# schemat.net
KiCad netlist of a schematic drawn in EAGLE
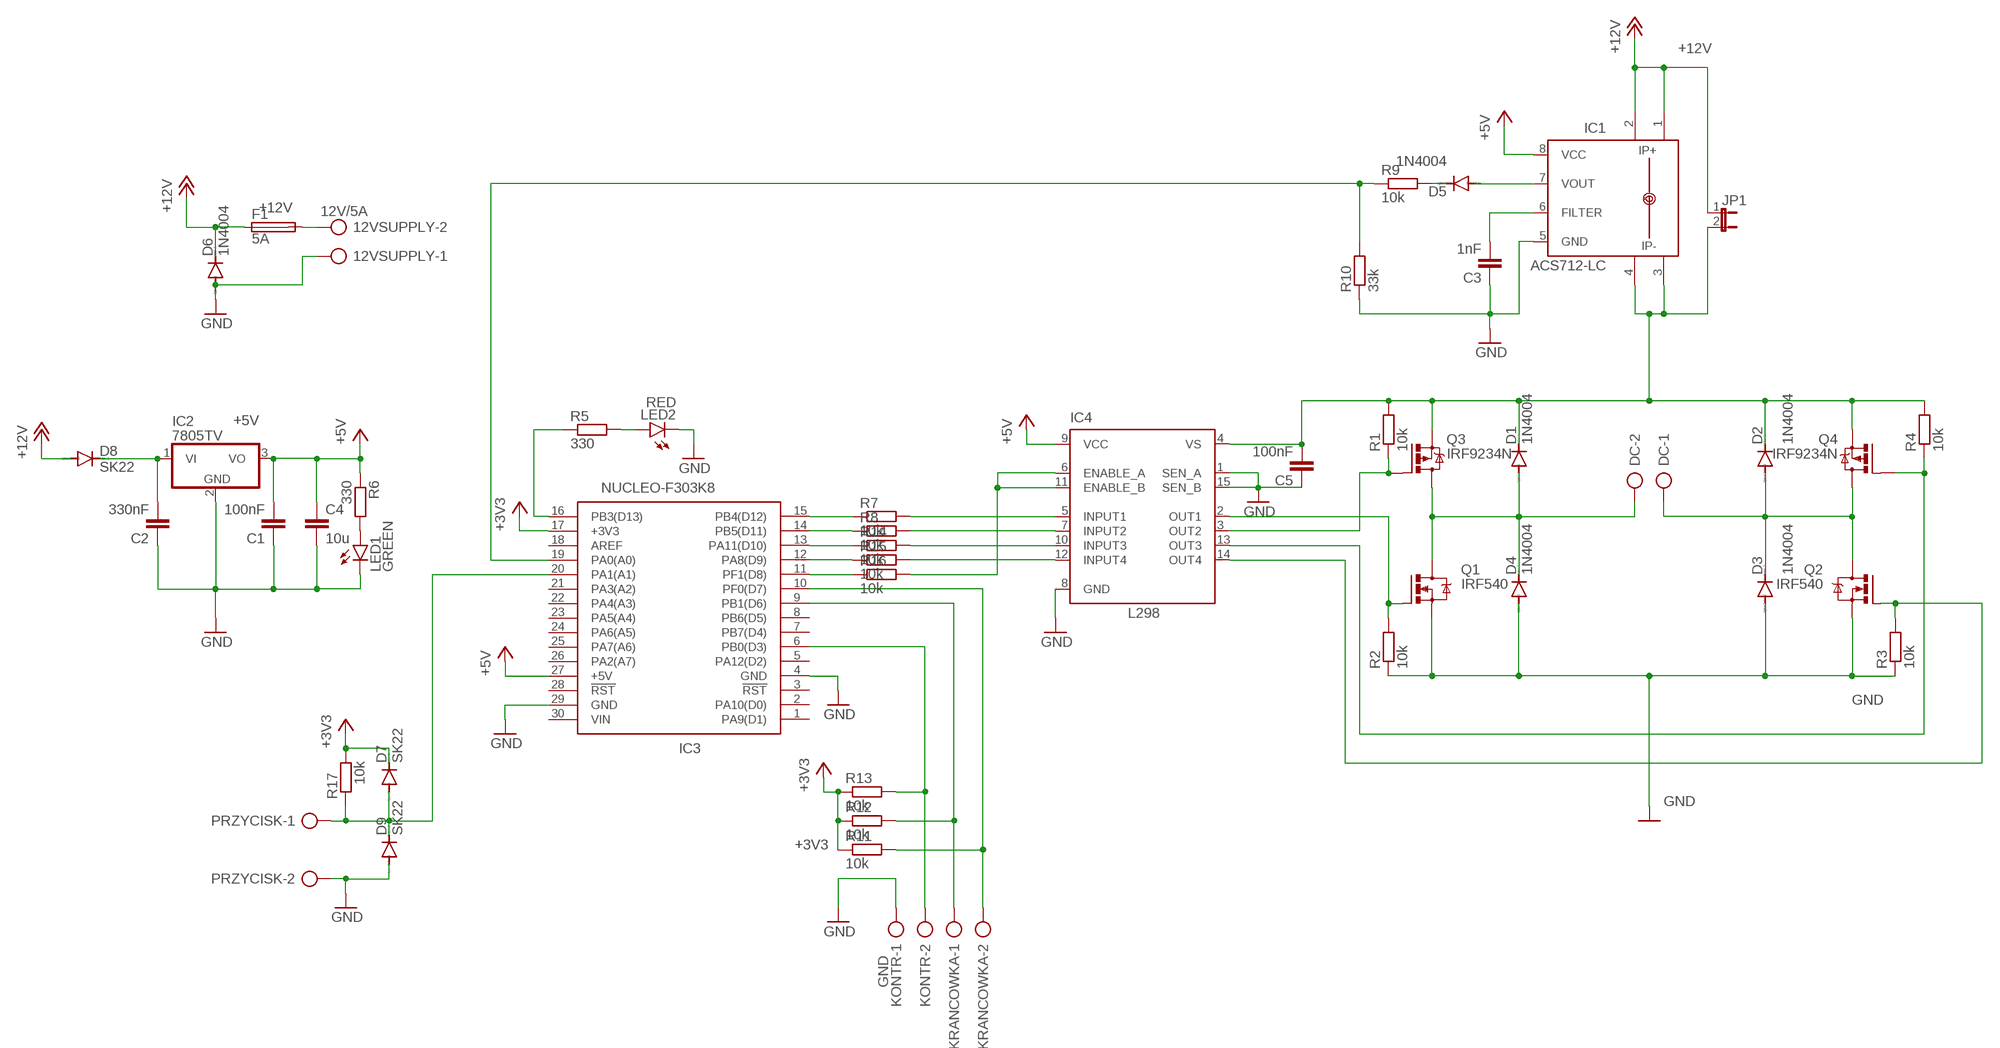
[diagram p0: schematic, sheet 1]

(export (version "E")
  (design (tool "Eeschema 10.0.6"))
  (components
    (comp (ref "12VSUPPLY")
      (value "12V/5A")
      (footprint "eagle-import:AK500_2-H")
      (libsource (lib "eagle-import") (part "AK500/2-H"))
    )
    (comp (ref "C1")
      (value "100nF")
      (footprint "eagle-import:C2.5-2")
      (libsource (lib "eagle-import") (part "C2.5/2"))
    )
    (comp (ref "C2")
      (value "330nF")
      (footprint "eagle-import:C2.5-2")
      (libsource (lib "eagle-import") (part "C2.5/2"))
    )
    (comp (ref "C3")
      (value "1nF")
      (footprint "eagle-import:C025-024X044")
      (libsource (lib "eagle-import") (part "C-EU025-024X044"))
    )
    (comp (ref "C4")
      (value "10u")
      (footprint "eagle-import:C025-024X044")
      (libsource (lib "eagle-import") (part "C-EU025-024X044"))
    )
    (comp (ref "C5")
      (value "100nF")
      (footprint "eagle-import:C2.5-2")
      (libsource (lib "eagle-import") (part "C2.5/2"))
    )
    (comp (ref "D1")
      (value "1N4004")
      (footprint "eagle-import:DO41-10")
      (libsource (lib "eagle-import") (part "1N4004"))
    )
    (comp (ref "D2")
      (value "1N4004")
      (footprint "eagle-import:DO41-10")
      (libsource (lib "eagle-import") (part "1N4004"))
    )
    (comp (ref "D3")
      (value "1N4004")
      (footprint "eagle-import:DO41-10")
      (libsource (lib "eagle-import") (part "1N4004"))
    )
    (comp (ref "D4")
      (value "1N4004")
      (footprint "eagle-import:DO41-10")
      (libsource (lib "eagle-import") (part "1N4004"))
    )
    (comp (ref "D5")
      (value "1N4004")
      (footprint "eagle-import:DO41-10")
      (libsource (lib "eagle-import") (part "1N4004"))
    )
    (comp (ref "D6")
      (value "1N4004")
      (footprint "eagle-import:DO41-10")
      (libsource (lib "eagle-import") (part "1N4004"))
    )
    (comp (ref "D7")
      (value "SK22")
      (footprint "eagle-import:SMB")
      (libsource (lib "eagle-import") (part "ES2D"))
    )
    (comp (ref "D8")
      (value "SK22")
      (footprint "eagle-import:SMB")
      (libsource (lib "eagle-import") (part "ES2D"))
    )
    (comp (ref "D9")
      (value "SK22")
      (footprint "eagle-import:SMB")
      (libsource (lib "eagle-import") (part "ES2D"))
    )
    (comp (ref "DC")
      (value "AK500/2-H")
      (footprint "eagle-import:AK500_2-H")
      (libsource (lib "eagle-import") (part "AK500/2-H"))
    )
    (comp (ref "F1")
      (value "5A")
      (footprint "eagle-import:TR5")
      (libsource (lib "eagle-import") (part "TR5"))
    )
    (comp (ref "IC1")
      (value "ACS712-LC")
      (footprint "eagle-import:SOIC8")
      (libsource (lib "eagle-import") (part "ACS712-LC"))
    )
    (comp (ref "IC2")
      (value "7805TV")
      (footprint "eagle-import:TO220V")
      (libsource (lib "eagle-import") (part "78TV05"))
    )
    (comp (ref "IC3")
      (value "NUCLEO-F303K8")
      (footprint "eagle-import:DIPS1524W66P254L5029H1500Q30N")
      (fields (field (name "RS_PART_NUMBER") "9092862"))
      (libsource (lib "eagle-import") (part "NUCLEO-F303K8"))
    )
    (comp (ref "IC4")
      (value "L298")
      (footprint "eagle-import:MULTIWATT-15")
      (fields (field (name "MPN") "L298N"))
      (libsource (lib "eagle-import") (part "L298"))
    )
    (comp (ref "JP1")
      (value "JP1E")
      (footprint "eagle-import:JP1")
      (libsource (lib "eagle-import") (part "JP1E"))
    )
    (comp (ref "KONTR")
      (value "GND")
      (footprint "eagle-import:AK500_2-H")
      (libsource (lib "eagle-import") (part "AK500/2-H"))
    )
    (comp (ref "KRANCOWKA")
      (value "AK500/2-H")
      (footprint "eagle-import:AK500_2-H")
      (libsource (lib "eagle-import") (part "AK500/2-H"))
    )
    (comp (ref "LED1")
      (value "GREEN")
      (footprint "eagle-import:LED3MM")
      (libsource (lib "eagle-import") (part "LED3MM"))
    )
    (comp (ref "LED2")
      (value "RED")
      (footprint "eagle-import:LED3MM")
      (libsource (lib "eagle-import") (part "LED3MM"))
    )
    (comp (ref "PRZYCISK")
      (value "AK500/2-H")
      (footprint "eagle-import:AK500_2-H")
      (libsource (lib "eagle-import") (part "AK500/2-H"))
    )
    (comp (ref "Q1")
      (value "IRF540")
      (footprint "eagle-import:TO220BV")
      (libsource (lib "eagle-import") (part "IRF540"))
    )
    (comp (ref "Q2")
      (value "IRF540")
      (footprint "eagle-import:TO220BV")
      (libsource (lib "eagle-import") (part "IRF540"))
    )
    (comp (ref "Q3")
      (value "IRF9234N")
      (footprint "eagle-import:TO220BV")
      (libsource (lib "eagle-import") (part "IRF9530"))
    )
    (comp (ref "Q4")
      (value "IRF9234N")
      (footprint "eagle-import:TO220BV")
      (libsource (lib "eagle-import") (part "IRF9530"))
    )
    (comp (ref "R1")
      (value "10k")
      (footprint "eagle-import:R1206")
      (libsource (lib "eagle-import") (part "R-EU_R1206"))
    )
    (comp (ref "R2")
      (value "10k")
      (footprint "eagle-import:R1206")
      (libsource (lib "eagle-import") (part "R-EU_R1206"))
    )
    (comp (ref "R3")
      (value "10k")
      (footprint "eagle-import:R1206")
      (libsource (lib "eagle-import") (part "R-EU_R1206"))
    )
    (comp (ref "R4")
      (value "10k")
      (footprint "eagle-import:R1206")
      (libsource (lib "eagle-import") (part "R-EU_R1206"))
    )
    (comp (ref "R5")
      (value "330")
      (footprint "eagle-import:R1206")
      (libsource (lib "eagle-import") (part "R-EU_R1206"))
    )
    (comp (ref "R6")
      (value "330")
      (footprint "eagle-import:R1206")
      (libsource (lib "eagle-import") (part "R-EU_R1206"))
    )
    (comp (ref "R7")
      (value "10k")
      (footprint "eagle-import:R1206")
      (libsource (lib "eagle-import") (part "R-EU_R1206"))
    )
    (comp (ref "R8")
      (value "10k")
      (footprint "eagle-import:R1206")
      (libsource (lib "eagle-import") (part "R-EU_R1206"))
    )
    (comp (ref "R9")
      (value "10k")
      (footprint "eagle-import:R1206")
      (libsource (lib "eagle-import") (part "R-EU_R1206"))
    )
    (comp (ref "R10")
      (value "33k")
      (footprint "eagle-import:R1206")
      (libsource (lib "eagle-import") (part "R-EU_R1206"))
    )
    (comp (ref "R11")
      (value "10k")
      (footprint "eagle-import:R1206")
      (libsource (lib "eagle-import") (part "R-EU_R1206"))
    )
    (comp (ref "R12")
      (value "10k")
      (footprint "eagle-import:R1206")
      (libsource (lib "eagle-import") (part "R-EU_R1206"))
    )
    (comp (ref "R13")
      (value "10k")
      (footprint "eagle-import:R1206")
      (libsource (lib "eagle-import") (part "R-EU_R1206"))
    )
    (comp (ref "R14")
      (value "10k")
      (footprint "eagle-import:R1206")
      (libsource (lib "eagle-import") (part "R-EU_R1206"))
    )
    (comp (ref "R15")
      (value "10k")
      (footprint "eagle-import:R1206")
      (libsource (lib "eagle-import") (part "R-EU_R1206"))
    )
    (comp (ref "R16")
      (value "10k")
      (footprint "eagle-import:R1206")
      (libsource (lib "eagle-import") (part "R-EU_R1206"))
    )
    (comp (ref "R17")
      (value "10k")
      (footprint "eagle-import:R1206")
      (libsource (lib "eagle-import") (part "R-EU_R1206"))
    )
  )
  (nets
    (net (code "1") (name "+3V3") (class "Default")
      (node (ref "D7") (pin "C") (pinfunction "C_C") (pintype "passive"))
      (node (ref "IC3") (pin "17") (pinfunction "+3V3_17") (pintype "passive"))
      (node (ref "R11") (pin "1") (pinfunction "1_1") (pintype "passive"))
      (node (ref "R12") (pin "1") (pinfunction "1_1") (pintype "passive"))
      (node (ref "R13") (pin "1") (pinfunction "1_1") (pintype "passive"))
      (node (ref "R17") (pin "2") (pinfunction "2_2") (pintype "passive"))
    )
    (net (code "2") (name "+5V") (class "Default")
      (node (ref "C1") (pin "2") (pinfunction "2_2") (pintype "passive"))
      (node (ref "C4") (pin "1") (pinfunction "1_1") (pintype "passive"))
      (node (ref "IC1") (pin "8") (pinfunction "VCC_8") (pintype "power_in"))
      (node (ref "IC2") (pin "3") (pinfunction "VO_3") (pintype "passive"))
      (node (ref "IC3") (pin "27") (pinfunction "+5V_27") (pintype "passive"))
      (node (ref "IC4") (pin "9") (pinfunction "VCC_9") (pintype "power_in"))
      (node (ref "R6") (pin "1") (pinfunction "1_1") (pintype "passive"))
    )
    (net (code "3") (name "+12V") (class "Default")
      (node (ref "D6") (pin "C") (pinfunction "C_C") (pintype "passive"))
      (node (ref "D8") (pin "A") (pinfunction "A_A") (pintype "passive"))
      (node (ref "F1") (pin "1") (pinfunction "1_1") (pintype "passive"))
      (node (ref "IC1") (pin "1") (pinfunction "IP+_1") (pintype "passive"))
      (node (ref "IC1") (pin "2") (pinfunction "IP+1_2") (pintype "passive"))
      (node (ref "JP1") (pin "1") (pinfunction "1_1") (pintype "passive"))
    )
    (net (code "4") (name "GND") (class "Default")
      (node (ref "12VSUPPLY") (pin "1") (pinfunction "KL_1") (pintype "passive"))
      (node (ref "C1") (pin "1") (pinfunction "1_1") (pintype "passive"))
      (node (ref "C2") (pin "1") (pinfunction "1_1") (pintype "passive"))
      (node (ref "C3") (pin "1") (pinfunction "1_1") (pintype "passive"))
      (node (ref "C4") (pin "2") (pinfunction "2_2") (pintype "passive"))
      (node (ref "C5") (pin "1") (pinfunction "1_1") (pintype "passive"))
      (node (ref "D3") (pin "A") (pinfunction "A_A") (pintype "passive"))
      (node (ref "D4") (pin "A") (pinfunction "A_A") (pintype "passive"))
      (node (ref "D6") (pin "A") (pinfunction "A_A") (pintype "passive"))
      (node (ref "D9") (pin "A") (pinfunction "A_A") (pintype "passive"))
      (node (ref "IC1") (pin "5") (pinfunction "GND_5") (pintype "power_in"))
      (node (ref "IC2") (pin "2") (pinfunction "GND_2") (pintype "passive"))
      (node (ref "IC3") (pin "29") (pinfunction "GND_29") (pintype "passive"))
      (node (ref "IC3") (pin "4") (pinfunction "GND_4") (pintype "passive"))
      (node (ref "IC4") (pin "1") (pinfunction "SEN_A_1") (pintype "input"))
      (node (ref "IC4") (pin "15") (pinfunction "SEN_B_15") (pintype "input"))
      (node (ref "IC4") (pin "8") (pinfunction "GND_8") (pintype "power_in"))
      (node (ref "KONTR") (pin "1") (pinfunction "KL_1") (pintype "passive"))
      (node (ref "LED1") (pin "K") (pinfunction "C_K") (pintype "passive"))
      (node (ref "LED2") (pin "K") (pinfunction "C_K") (pintype "passive"))
      (node (ref "PRZYCISK") (pin "2") (pinfunction "KL_2") (pintype "passive"))
      (node (ref "Q1") (pin "S") (pinfunction "S_S") (pintype "passive"))
      (node (ref "Q2") (pin "S") (pinfunction "S_S") (pintype "passive"))
      (node (ref "R10") (pin "1") (pinfunction "1_1") (pintype "passive"))
      (node (ref "R2") (pin "1") (pinfunction "1_1") (pintype "passive"))
      (node (ref "R3") (pin "1") (pinfunction "1_1") (pintype "passive"))
    )
    (net (code "5") (name "Net-(12VSUPPLYB-KL)") (class "Default")
      (node (ref "12VSUPPLY") (pin "2") (pinfunction "KL_2") (pintype "passive"))
      (node (ref "F1") (pin "2") (pinfunction "2_2") (pintype "passive"))
    )
    (net (code "6") (name "Net-(D5-PadC)") (class "Default")
      (node (ref "D5") (pin "C") (pinfunction "C_C") (pintype "passive"))
      (node (ref "R9") (pin "2") (pinfunction "2_2") (pintype "passive"))
    )
    (net (code "7") (name "Net-(DCA-KL)") (class "Default")
      (node (ref "D2") (pin "A") (pinfunction "A_A") (pintype "passive"))
      (node (ref "D3") (pin "C") (pinfunction "C_C") (pintype "passive"))
      (node (ref "DC") (pin "1") (pinfunction "KL_1") (pintype "passive"))
      (node (ref "Q2") (pin "D") (pinfunction "D_D") (pintype "passive"))
      (node (ref "Q4") (pin "D") (pinfunction "D_D") (pintype "passive"))
    )
    (net (code "8") (name "Net-(DCB-KL)") (class "Default")
      (node (ref "D1") (pin "A") (pinfunction "A_A") (pintype "passive"))
      (node (ref "D4") (pin "C") (pinfunction "C_C") (pintype "passive"))
      (node (ref "DC") (pin "2") (pinfunction "KL_2") (pintype "passive"))
      (node (ref "Q1") (pin "D") (pinfunction "D_D") (pintype "passive"))
      (node (ref "Q3") (pin "D") (pinfunction "D_D") (pintype "passive"))
    )
    (net (code "9") (name "Net-(IC1-FILTER)") (class "Default")
      (node (ref "C3") (pin "2") (pinfunction "2_2") (pintype "passive"))
      (node (ref "IC1") (pin "6") (pinfunction "FILTER_6") (pintype "bidirectional"))
    )
    (net (code "10") (name "Net-(IC1-IP-)") (class "Default")
      (node (ref "C5") (pin "2") (pinfunction "2_2") (pintype "passive"))
      (node (ref "D1") (pin "C") (pinfunction "C_C") (pintype "passive"))
      (node (ref "D2") (pin "C") (pinfunction "C_C") (pintype "passive"))
      (node (ref "IC1") (pin "3") (pinfunction "IP-_3") (pintype "passive"))
      (node (ref "IC1") (pin "4") (pinfunction "IP-1_4") (pintype "passive"))
      (node (ref "IC4") (pin "4") (pinfunction "VS_4") (pintype "power_in"))
      (node (ref "JP1") (pin "2") (pinfunction "2_2") (pintype "passive"))
      (node (ref "Q3") (pin "S") (pinfunction "S_S") (pintype "passive"))
      (node (ref "Q4") (pin "S") (pinfunction "S_S") (pintype "passive"))
      (node (ref "R1") (pin "2") (pinfunction "2_2") (pintype "passive"))
      (node (ref "R4") (pin "2") (pinfunction "2_2") (pintype "passive"))
    )
    (net (code "11") (name "Net-(IC1-VOUT)") (class "Default")
      (node (ref "D5") (pin "A") (pinfunction "A_A") (pintype "passive"))
      (node (ref "IC1") (pin "7") (pinfunction "VOUT_7") (pintype "output"))
    )
    (net (code "12") (name "Net-(IC2-VI)") (class "Default")
      (node (ref "C2") (pin "2") (pinfunction "2_2") (pintype "passive"))
      (node (ref "D8") (pin "C") (pinfunction "C_C") (pintype "passive"))
      (node (ref "IC2") (pin "1") (pinfunction "VI_1") (pintype "input"))
    )
    (net (code "13") (name "Net-(IC3-PA0(A0))") (class "Default")
      (node (ref "IC3") (pin "19") (pinfunction "PA0(A0)_19") (pintype "bidirectional"))
      (node (ref "R10") (pin "2") (pinfunction "2_2") (pintype "passive"))
      (node (ref "R9") (pin "1") (pinfunction "1_1") (pintype "passive"))
    )
    (net (code "14") (name "Net-(IC3-PA1(A1))") (class "Default")
      (node (ref "D7") (pin "A") (pinfunction "A_A") (pintype "passive"))
      (node (ref "D9") (pin "C") (pinfunction "C_C") (pintype "passive"))
      (node (ref "IC3") (pin "20") (pinfunction "PA1(A1)_20") (pintype "bidirectional"))
      (node (ref "PRZYCISK") (pin "1") (pinfunction "KL_1") (pintype "passive"))
      (node (ref "R17") (pin "1") (pinfunction "1_1") (pintype "passive"))
    )
    (net (code "15") (name "Net-(IC3-PA8(D9))") (class "Default")
      (node (ref "IC3") (pin "12") (pinfunction "PA8(D9)_12") (pintype "bidirectional"))
      (node (ref "R15") (pin "1") (pinfunction "1_1") (pintype "passive"))
    )
    (net (code "16") (name "Net-(IC3-PA11(D10))") (class "Default")
      (node (ref "IC3") (pin "13") (pinfunction "PA11(D10)_13") (pintype "bidirectional"))
      (node (ref "R14") (pin "1") (pinfunction "1_1") (pintype "passive"))
    )
    (net (code "17") (name "Net-(IC3-PB0(D3))") (class "Default")
      (node (ref "IC3") (pin "6") (pinfunction "PB0(D3)_6") (pintype "bidirectional"))
      (node (ref "KONTR") (pin "2") (pinfunction "KL_2") (pintype "passive"))
      (node (ref "R13") (pin "2") (pinfunction "2_2") (pintype "passive"))
    )
    (net (code "18") (name "Net-(IC3-PB1(D6))") (class "Default")
      (node (ref "IC3") (pin "9") (pinfunction "PB1(D6)_9") (pintype "bidirectional"))
      (node (ref "KRANCOWKA") (pin "1") (pinfunction "KL_1") (pintype "passive"))
      (node (ref "R12") (pin "2") (pinfunction "2_2") (pintype "passive"))
    )
    (net (code "19") (name "Net-(IC3-PB3(D13))") (class "Default")
      (node (ref "IC3") (pin "16") (pinfunction "PB3(D13)_16") (pintype "bidirectional"))
      (node (ref "R5") (pin "1") (pinfunction "1_1") (pintype "passive"))
    )
    (net (code "20") (name "Net-(IC3-PB4(D12))") (class "Default")
      (node (ref "IC3") (pin "15") (pinfunction "PB4(D12)_15") (pintype "bidirectional"))
      (node (ref "R7") (pin "1") (pinfunction "1_1") (pintype "passive"))
    )
    (net (code "21") (name "Net-(IC3-PB5(D11))") (class "Default")
      (node (ref "IC3") (pin "14") (pinfunction "PB5(D11)_14") (pintype "bidirectional"))
      (node (ref "R8") (pin "1") (pinfunction "1_1") (pintype "passive"))
    )
    (net (code "22") (name "Net-(IC3-PF0(D7))") (class "Default")
      (node (ref "IC3") (pin "10") (pinfunction "PF0(D7)_10") (pintype "bidirectional"))
      (node (ref "KRANCOWKA") (pin "2") (pinfunction "KL_2") (pintype "passive"))
      (node (ref "R11") (pin "2") (pinfunction "2_2") (pintype "passive"))
    )
    (net (code "23") (name "Net-(IC3-PF1(D8))") (class "Default")
      (node (ref "IC3") (pin "11") (pinfunction "PF1(D8)_11") (pintype "bidirectional"))
      (node (ref "R16") (pin "1") (pinfunction "1_1") (pintype "passive"))
    )
    (net (code "24") (name "Net-(IC4-ENABLE_A)") (class "Default")
      (node (ref "IC4") (pin "11") (pinfunction "ENABLE_B_11") (pintype "input"))
      (node (ref "IC4") (pin "6") (pinfunction "ENABLE_A_6") (pintype "input"))
      (node (ref "R16") (pin "2") (pinfunction "2_2") (pintype "passive"))
    )
    (net (code "25") (name "Net-(IC4-INPUT1)") (class "Default")
      (node (ref "IC4") (pin "5") (pinfunction "INPUT1_5") (pintype "input"))
      (node (ref "R7") (pin "2") (pinfunction "2_2") (pintype "passive"))
    )
    (net (code "26") (name "Net-(IC4-INPUT2)") (class "Default")
      (node (ref "IC4") (pin "7") (pinfunction "INPUT2_7") (pintype "input"))
      (node (ref "R8") (pin "2") (pinfunction "2_2") (pintype "passive"))
    )
    (net (code "27") (name "Net-(IC4-INPUT3)") (class "Default")
      (node (ref "IC4") (pin "10") (pinfunction "INPUT3_10") (pintype "input"))
      (node (ref "R14") (pin "2") (pinfunction "2_2") (pintype "passive"))
    )
    (net (code "28") (name "Net-(IC4-INPUT4)") (class "Default")
      (node (ref "IC4") (pin "12") (pinfunction "INPUT4_12") (pintype "input"))
      (node (ref "R15") (pin "2") (pinfunction "2_2") (pintype "passive"))
    )
    (net (code "29") (name "Net-(IC4-OUT1)") (class "Default")
      (node (ref "IC4") (pin "2") (pinfunction "OUT1_2") (pintype "output"))
      (node (ref "Q1") (pin "G") (pinfunction "G_G") (pintype "passive"))
      (node (ref "R2") (pin "2") (pinfunction "2_2") (pintype "passive"))
    )
    (net (code "30") (name "Net-(IC4-OUT2)") (class "Default")
      (node (ref "IC4") (pin "3") (pinfunction "OUT2_3") (pintype "output"))
      (node (ref "Q3") (pin "G") (pinfunction "G_G") (pintype "passive"))
      (node (ref "R1") (pin "1") (pinfunction "1_1") (pintype "passive"))
    )
    (net (code "31") (name "Net-(IC4-OUT3)") (class "Default")
      (node (ref "IC4") (pin "13") (pinfunction "OUT3_13") (pintype "output"))
      (node (ref "Q4") (pin "G") (pinfunction "G_G") (pintype "passive"))
      (node (ref "R4") (pin "1") (pinfunction "1_1") (pintype "passive"))
    )
    (net (code "32") (name "Net-(IC4-OUT4)") (class "Default")
      (node (ref "IC4") (pin "14") (pinfunction "OUT4_14") (pintype "output"))
      (node (ref "Q2") (pin "G") (pinfunction "G_G") (pintype "passive"))
      (node (ref "R3") (pin "2") (pinfunction "2_2") (pintype "passive"))
    )
    (net (code "33") (name "Net-(LED1-PadA)") (class "Default")
      (node (ref "LED1") (pin "A") (pinfunction "A_A") (pintype "passive"))
      (node (ref "R6") (pin "2") (pinfunction "2_2") (pintype "passive"))
    )
    (net (code "34") (name "Net-(LED2-PadA)") (class "Default")
      (node (ref "LED2") (pin "A") (pinfunction "A_A") (pintype "passive"))
      (node (ref "R5") (pin "2") (pinfunction "2_2") (pintype "passive"))
    )
    (net (code "35") (name "unconnected-(IC3-AREF-Pad18)") (class "Default")
      (node (ref "IC3") (pin "18") (pinfunction "AREF_18") (pintype "passive"))
    )
    (net (code "36") (name "unconnected-(IC3-PA2(A7)-Pad26)") (class "Default")
      (node (ref "IC3") (pin "26") (pinfunction "PA2(A7)_26") (pintype "bidirectional"))
    )
    (net (code "37") (name "unconnected-(IC3-PA3(A2)-Pad21)") (class "Default")
      (node (ref "IC3") (pin "21") (pinfunction "PA3(A2)_21") (pintype "bidirectional"))
    )
    (net (code "38") (name "unconnected-(IC3-PA4(A3)-Pad22)") (class "Default")
      (node (ref "IC3") (pin "22") (pinfunction "PA4(A3)_22") (pintype "bidirectional"))
    )
    (net (code "39") (name "unconnected-(IC3-PA5(A4)-Pad23)") (class "Default")
      (node (ref "IC3") (pin "23") (pinfunction "PA5(A4)_23") (pintype "bidirectional"))
    )
    (net (code "40") (name "unconnected-(IC3-PA6(A5)-Pad24)") (class "Default")
      (node (ref "IC3") (pin "24") (pinfunction "PA6(A5)_24") (pintype "bidirectional"))
    )
    (net (code "41") (name "unconnected-(IC3-PA7(A6)-Pad25)") (class "Default")
      (node (ref "IC3") (pin "25") (pinfunction "PA7(A6)_25") (pintype "bidirectional"))
    )
    (net (code "42") (name "unconnected-(IC3-PA9(D1)-Pad1)") (class "Default")
      (node (ref "IC3") (pin "1") (pinfunction "PA9(D1)_1") (pintype "bidirectional"))
    )
    (net (code "43") (name "unconnected-(IC3-PA10(D0)-Pad2)") (class "Default")
      (node (ref "IC3") (pin "2") (pinfunction "PA10(D0)_2") (pintype "bidirectional"))
    )
    (net (code "44") (name "unconnected-(IC3-PA12(D2)-Pad5)") (class "Default")
      (node (ref "IC3") (pin "5") (pinfunction "PA12(D2)_5") (pintype "bidirectional"))
    )
    (net (code "45") (name "unconnected-(IC3-PB6(D5)-Pad8)") (class "Default")
      (node (ref "IC3") (pin "8") (pinfunction "PB6(D5)_8") (pintype "bidirectional"))
    )
    (net (code "46") (name "unconnected-(IC3-PB7(D4)-Pad7)") (class "Default")
      (node (ref "IC3") (pin "7") (pinfunction "PB7(D4)_7") (pintype "bidirectional"))
    )
    (net (code "47") (name "unconnected-(IC3-VIN-Pad30)") (class "Default")
      (node (ref "IC3") (pin "30") (pinfunction "VIN_30") (pintype "passive"))
    )
    (net (code "48") (name "unconnected-(IC3-~{RST}-Pad3)") (class "Default")
      (node (ref "IC3") (pin "3") (pinfunction "~{RST}_3") (pintype "bidirectional"))
    )
    (net (code "49") (name "unconnected-(IC3-~{RST}-Pad28)") (class "Default")
      (node (ref "IC3") (pin "28") (pinfunction "~{RST}_28") (pintype "bidirectional"))
    )
  )
)
